# JoyStickAdcInput.net
KiCad netlist of a schematic drawn in Altium Designer
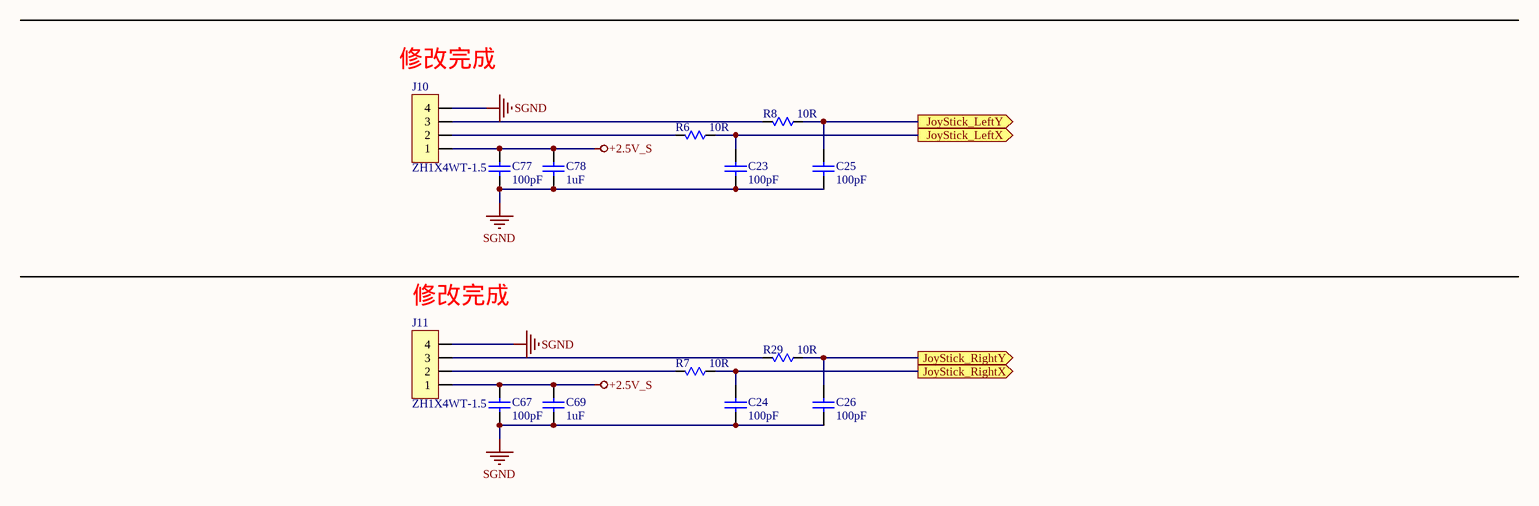
[diagram p0: JoyStickAdcInput.SchDoc]

(export (version "E")
  (design (tool "Eeschema 10.0.6"))
  (components
    (comp (ref "C23")
      (value "100pF")
      (footprint "C0805")
      (description "Capacitor")
      (fields (field (name "PUBLISHER") "Altium Limited"))
      (libsource (lib "Miscellaneous Devices") (part "Cap"))
    )
    (comp (ref "C24")
      (value "100pF")
      (footprint "C0805")
      (description "Capacitor")
      (fields (field (name "PUBLISHER") "Altium Limited"))
      (libsource (lib "Miscellaneous Devices") (part "Cap"))
    )
    (comp (ref "C25")
      (value "100pF")
      (footprint "C0805")
      (description "Capacitor")
      (fields (field (name "PUBLISHER") "Altium Limited"))
      (libsource (lib "Miscellaneous Devices") (part "Cap"))
    )
    (comp (ref "C26")
      (value "100pF")
      (footprint "C0805")
      (description "Capacitor")
      (fields (field (name "PUBLISHER") "Altium Limited"))
      (libsource (lib "Miscellaneous Devices") (part "Cap"))
    )
    (comp (ref "C67")
      (value "100pF")
      (footprint "C0805")
      (description "Capacitor")
      (fields (field (name "PUBLISHER") "Altium Limited"))
      (libsource (lib "Miscellaneous Devices") (part "Cap"))
    )
    (comp (ref "C69")
      (value "1uF")
      (footprint "C0805")
      (description "Capacitor")
      (fields (field (name "PUBLISHER") "Altium Limited"))
      (libsource (lib "Miscellaneous Devices") (part "Cap"))
    )
    (comp (ref "C77")
      (value "100pF")
      (footprint "C0805")
      (description "Capacitor")
      (fields (field (name "PUBLISHER") "Altium Limited"))
      (libsource (lib "Miscellaneous Devices") (part "Cap"))
    )
    (comp (ref "C78")
      (value "1uF")
      (footprint "C0805")
      (description "Capacitor")
      (fields (field (name "PUBLISHER") "Altium Limited"))
      (libsource (lib "Miscellaneous Devices") (part "Cap"))
    )
    (comp (ref "J10")
      (value "ZH1X4WT-1.5")
      (footprint "ZH1X4WT-1.5")
      (libsource (lib "Connector Class") (part "HEADER1X4"))
    )
    (comp (ref "J11")
      (value "ZH1X4WT-1.5")
      (footprint "ZH1X4WT-1.5")
      (libsource (lib "Connector Class") (part "HEADER1X4"))
    )
    (comp (ref "R6")
      (value "10R")
      (footprint "R0805")
      (description "Resistor")
      (fields (field (name "PUBLISHER") "Altium Limited"))
      (libsource (lib "Passive Components Class") (part "RES"))
    )
    (comp (ref "R7")
      (value "10R")
      (footprint "R0805")
      (description "Resistor")
      (fields (field (name "PUBLISHER") "Altium Limited"))
      (libsource (lib "Passive Components Class") (part "RES"))
    )
    (comp (ref "R8")
      (value "10R")
      (footprint "R0805")
      (description "Resistor")
      (fields (field (name "PUBLISHER") "Altium Limited"))
      (libsource (lib "Passive Components Class") (part "RES"))
    )
    (comp (ref "R29")
      (value "10R")
      (footprint "R0805")
      (description "Resistor")
      (fields (field (name "PUBLISHER") "Altium Limited"))
      (libsource (lib "Passive Components Class") (part "RES"))
    )
  )
  (nets
    (net (code "1") (name "+2.5V_S") (class "Default")
      (node (ref "C67") (pin "1") (pinfunction "1_1") (pintype "passive"))
      (node (ref "C69") (pin "1") (pinfunction "1_1") (pintype "passive"))
      (node (ref "C77") (pin "1") (pinfunction "1_1") (pintype "passive"))
      (node (ref "C78") (pin "1") (pinfunction "1_1") (pintype "passive"))
      (node (ref "J10") (pin "1") (pinfunction "1_1") (pintype "passive"))
      (node (ref "J11") (pin "1") (pinfunction "1_1") (pintype "passive"))
    )
    (net (code "2") (name "/JoyStick_LeftX") (class "Default")
      (node (ref "C23") (pin "1") (pinfunction "1_1") (pintype "passive"))
      (node (ref "R6") (pin "1") (pinfunction "1_1") (pintype "passive"))
    )
    (net (code "3") (name "/JoyStick_LeftY") (class "Default")
      (node (ref "C25") (pin "1") (pinfunction "1_1") (pintype "passive"))
      (node (ref "R8") (pin "1") (pinfunction "1_1") (pintype "passive"))
    )
    (net (code "4") (name "/JoyStick_RightX") (class "Default")
      (node (ref "C24") (pin "1") (pinfunction "1_1") (pintype "passive"))
      (node (ref "R7") (pin "1") (pinfunction "1_1") (pintype "passive"))
    )
    (net (code "5") (name "/JoyStick_RightY") (class "Default")
      (node (ref "C26") (pin "1") (pinfunction "1_1") (pintype "passive"))
      (node (ref "R29") (pin "1") (pinfunction "1_1") (pintype "passive"))
    )
    (net (code "6") (name "Net-(J10-Pad2)") (class "Default")
      (node (ref "J10") (pin "2") (pinfunction "2_2") (pintype "passive"))
      (node (ref "R6") (pin "2") (pinfunction "2_2") (pintype "passive"))
    )
    (net (code "7") (name "Net-(J10-Pad3)") (class "Default")
      (node (ref "J10") (pin "3") (pinfunction "3_3") (pintype "passive"))
      (node (ref "R8") (pin "2") (pinfunction "2_2") (pintype "passive"))
    )
    (net (code "8") (name "Net-(J11-Pad2)") (class "Default")
      (node (ref "J11") (pin "2") (pinfunction "2_2") (pintype "passive"))
      (node (ref "R7") (pin "2") (pinfunction "2_2") (pintype "passive"))
    )
    (net (code "9") (name "Net-(J11-Pad3)") (class "Default")
      (node (ref "J11") (pin "3") (pinfunction "3_3") (pintype "passive"))
      (node (ref "R29") (pin "2") (pinfunction "2_2") (pintype "passive"))
    )
    (net (code "10") (name "SGND") (class "Default")
      (node (ref "C23") (pin "2") (pinfunction "2_2") (pintype "passive"))
      (node (ref "C24") (pin "2") (pinfunction "2_2") (pintype "passive"))
      (node (ref "C25") (pin "2") (pinfunction "2_2") (pintype "passive"))
      (node (ref "C26") (pin "2") (pinfunction "2_2") (pintype "passive"))
      (node (ref "C67") (pin "2") (pinfunction "2_2") (pintype "passive"))
      (node (ref "C69") (pin "2") (pinfunction "2_2") (pintype "passive"))
      (node (ref "C77") (pin "2") (pinfunction "2_2") (pintype "passive"))
      (node (ref "C78") (pin "2") (pinfunction "2_2") (pintype "passive"))
      (node (ref "J10") (pin "4") (pinfunction "4_4") (pintype "passive"))
      (node (ref "J11") (pin "4") (pinfunction "4_4") (pintype "passive"))
    )
  )
)
